# SDADC.net
KiCad netlist of a schematic drawn in Altium Designer
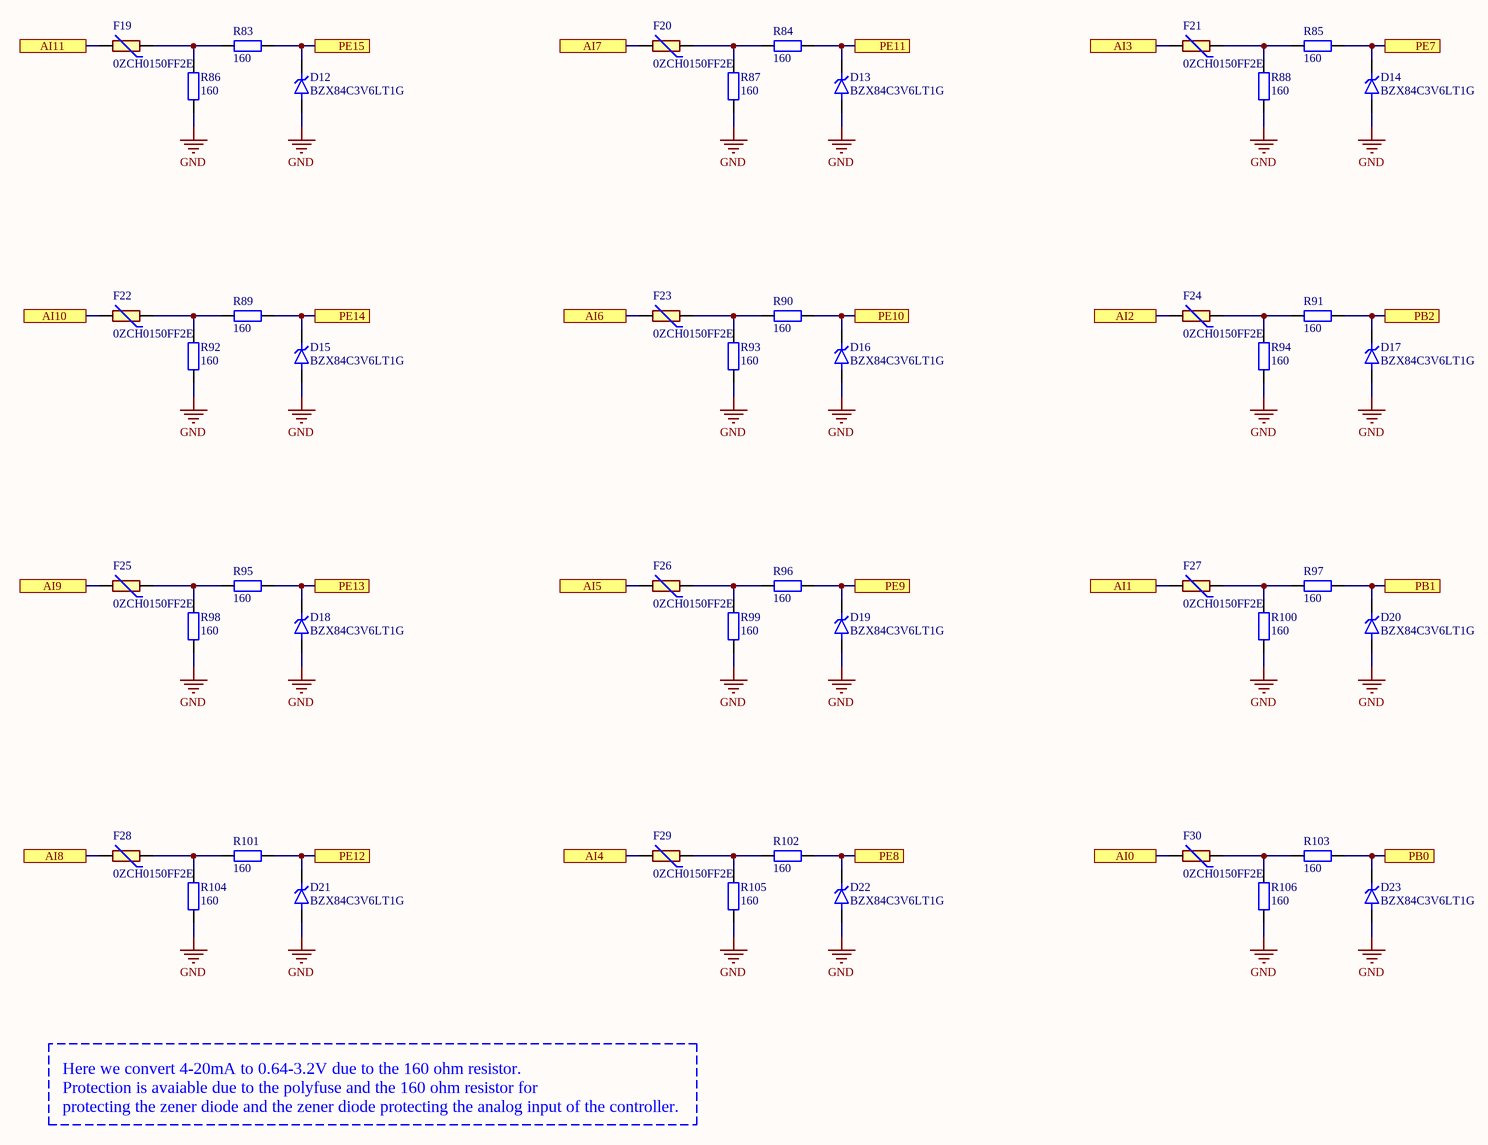
[diagram p0: SDADC.SchDoc]

(export (version "E")
  (design (tool "Eeschema 10.0.6"))
  (components
    (comp (ref "D12")
      (value "BZX84C3V6LT1G")
      (footprint "SOT95P240X111-3N")
      (libsource (lib "BZX84C3V6LT1G") (part "BZX84C3V6LT1G"))
    )
    (comp (ref "D13")
      (value "BZX84C3V6LT1G")
      (footprint "SOT95P240X111-3N")
      (libsource (lib "BZX84C3V6LT1G") (part "BZX84C3V6LT1G"))
    )
    (comp (ref "D14")
      (value "BZX84C3V6LT1G")
      (footprint "SOT95P240X111-3N")
      (libsource (lib "BZX84C3V6LT1G") (part "BZX84C3V6LT1G"))
    )
    (comp (ref "D15")
      (value "BZX84C3V6LT1G")
      (footprint "SOT95P240X111-3N")
      (libsource (lib "BZX84C3V6LT1G") (part "BZX84C3V6LT1G"))
    )
    (comp (ref "D16")
      (value "BZX84C3V6LT1G")
      (footprint "SOT95P240X111-3N")
      (libsource (lib "BZX84C3V6LT1G") (part "BZX84C3V6LT1G"))
    )
    (comp (ref "D17")
      (value "BZX84C3V6LT1G")
      (footprint "SOT95P240X111-3N")
      (libsource (lib "BZX84C3V6LT1G") (part "BZX84C3V6LT1G"))
    )
    (comp (ref "D18")
      (value "BZX84C3V6LT1G")
      (footprint "SOT95P240X111-3N")
      (libsource (lib "BZX84C3V6LT1G") (part "BZX84C3V6LT1G"))
    )
    (comp (ref "D19")
      (value "BZX84C3V6LT1G")
      (footprint "SOT95P240X111-3N")
      (libsource (lib "BZX84C3V6LT1G") (part "BZX84C3V6LT1G"))
    )
    (comp (ref "D20")
      (value "BZX84C3V6LT1G")
      (footprint "SOT95P240X111-3N")
      (libsource (lib "BZX84C3V6LT1G") (part "BZX84C3V6LT1G"))
    )
    (comp (ref "D21")
      (value "BZX84C3V6LT1G")
      (footprint "SOT95P240X111-3N")
      (libsource (lib "BZX84C3V6LT1G") (part "BZX84C3V6LT1G"))
    )
    (comp (ref "D22")
      (value "BZX84C3V6LT1G")
      (footprint "SOT95P240X111-3N")
      (libsource (lib "BZX84C3V6LT1G") (part "BZX84C3V6LT1G"))
    )
    (comp (ref "D23")
      (value "BZX84C3V6LT1G")
      (footprint "SOT95P240X111-3N")
      (libsource (lib "BZX84C3V6LT1G") (part "BZX84C3V6LT1G"))
    )
    (comp (ref "F19")
      (value "0ZCH0150FF2E")
      (footprint "FUSC3225X90N")
      (description "1210 SMT PPTC ¦ 1.50 Ih ¦ 6V")
      (fields (field (name "MF") "Bel Fuse"))
      (libsource (lib "") (part "0ZCH0150FF2E_1"))
    )
    (comp (ref "F20")
      (value "0ZCH0150FF2E")
      (footprint "FUSC3225X90N")
      (description "1210 SMT PPTC ¦ 1.50 Ih ¦ 6V")
      (fields (field (name "MF") "Bel Fuse"))
      (libsource (lib "") (part "0ZCH0150FF2E_1"))
    )
    (comp (ref "F21")
      (value "0ZCH0150FF2E")
      (footprint "FUSC3225X90N")
      (description "1210 SMT PPTC ¦ 1.50 Ih ¦ 6V")
      (fields (field (name "MF") "Bel Fuse"))
      (libsource (lib "0ZCH0150FF2E") (part "0ZCH0150FF2E"))
    )
    (comp (ref "F22")
      (value "0ZCH0150FF2E")
      (footprint "FUSC3225X90N")
      (description "1210 SMT PPTC ¦ 1.50 Ih ¦ 6V")
      (fields (field (name "MF") "Bel Fuse"))
      (libsource (lib "") (part "0ZCH0150FF2E_1"))
    )
    (comp (ref "F23")
      (value "0ZCH0150FF2E")
      (footprint "FUSC3225X90N")
      (description "1210 SMT PPTC ¦ 1.50 Ih ¦ 6V")
      (fields (field (name "MF") "Bel Fuse"))
      (libsource (lib "") (part "0ZCH0150FF2E_1"))
    )
    (comp (ref "F24")
      (value "0ZCH0150FF2E")
      (footprint "FUSC3225X90N")
      (description "1210 SMT PPTC ¦ 1.50 Ih ¦ 6V")
      (fields (field (name "MF") "Bel Fuse"))
      (libsource (lib "0ZCH0150FF2E") (part "0ZCH0150FF2E"))
    )
    (comp (ref "F25")
      (value "0ZCH0150FF2E")
      (footprint "FUSC3225X90N")
      (description "1210 SMT PPTC ¦ 1.50 Ih ¦ 6V")
      (fields (field (name "MF") "Bel Fuse"))
      (libsource (lib "") (part "0ZCH0150FF2E_1"))
    )
    (comp (ref "F26")
      (value "0ZCH0150FF2E")
      (footprint "FUSC3225X90N")
      (description "1210 SMT PPTC ¦ 1.50 Ih ¦ 6V")
      (fields (field (name "MF") "Bel Fuse"))
      (libsource (lib "") (part "0ZCH0150FF2E_1"))
    )
    (comp (ref "F27")
      (value "0ZCH0150FF2E")
      (footprint "FUSC3225X90N")
      (description "1210 SMT PPTC ¦ 1.50 Ih ¦ 6V")
      (fields (field (name "MF") "Bel Fuse"))
      (libsource (lib "0ZCH0150FF2E") (part "0ZCH0150FF2E"))
    )
    (comp (ref "F28")
      (value "0ZCH0150FF2E")
      (footprint "FUSC3225X90N")
      (description "1210 SMT PPTC ¦ 1.50 Ih ¦ 6V")
      (fields (field (name "MF") "Bel Fuse"))
      (libsource (lib "") (part "0ZCH0150FF2E_1"))
    )
    (comp (ref "F29")
      (value "0ZCH0150FF2E")
      (footprint "FUSC3225X90N")
      (description "1210 SMT PPTC ¦ 1.50 Ih ¦ 6V")
      (fields (field (name "MF") "Bel Fuse"))
      (libsource (lib "") (part "0ZCH0150FF2E_1"))
    )
    (comp (ref "F30")
      (value "0ZCH0150FF2E")
      (footprint "FUSC3225X90N")
      (description "1210 SMT PPTC ¦ 1.50 Ih ¦ 6V")
      (fields (field (name "MF") "Bel Fuse"))
      (libsource (lib "0ZCH0150FF2E") (part "0ZCH0150FF2E"))
    )
    (comp (ref "R83")
      (value "160")
      (footprint "tro smd 0603")
      (description "RES")
      (libsource (lib "AUSB") (part "Tro 0603 1% 10k"))
    )
    (comp (ref "R84")
      (value "160")
      (footprint "tro smd 0603")
      (description "RES")
      (libsource (lib "AUSB") (part "Tro 0603 1% 10k"))
    )
    (comp (ref "R85")
      (value "160")
      (footprint "tro smd 0603")
      (description "RES")
      (libsource (lib "AUSB") (part "Tro 0603 1% 10k"))
    )
    (comp (ref "R86")
      (value "160")
      (footprint "tro smd 0603")
      (description "RES")
      (libsource (lib "AUSB") (part "Tro 0603 1% 10k"))
    )
    (comp (ref "R87")
      (value "160")
      (footprint "tro smd 0603")
      (description "RES")
      (libsource (lib "AUSB") (part "Tro 0603 1% 10k"))
    )
    (comp (ref "R88")
      (value "160")
      (footprint "tro smd 0603")
      (description "RES")
      (libsource (lib "AUSB") (part "Tro 0603 1% 10k"))
    )
    (comp (ref "R89")
      (value "160")
      (footprint "tro smd 0603")
      (description "RES")
      (libsource (lib "AUSB") (part "Tro 0603 1% 10k"))
    )
    (comp (ref "R90")
      (value "160")
      (footprint "tro smd 0603")
      (description "RES")
      (libsource (lib "AUSB") (part "Tro 0603 1% 10k"))
    )
    (comp (ref "R91")
      (value "160")
      (footprint "tro smd 0603")
      (description "RES")
      (libsource (lib "AUSB") (part "Tro 0603 1% 10k"))
    )
    (comp (ref "R92")
      (value "160")
      (footprint "tro smd 0603")
      (description "RES")
      (libsource (lib "AUSB") (part "Tro 0603 1% 10k"))
    )
    (comp (ref "R93")
      (value "160")
      (footprint "tro smd 0603")
      (description "RES")
      (libsource (lib "AUSB") (part "Tro 0603 1% 10k"))
    )
    (comp (ref "R94")
      (value "160")
      (footprint "tro smd 0603")
      (description "RES")
      (libsource (lib "AUSB") (part "Tro 0603 1% 10k"))
    )
    (comp (ref "R95")
      (value "160")
      (footprint "tro smd 0603")
      (description "RES")
      (libsource (lib "AUSB") (part "Tro 0603 1% 10k"))
    )
    (comp (ref "R96")
      (value "160")
      (footprint "tro smd 0603")
      (description "RES")
      (libsource (lib "AUSB") (part "Tro 0603 1% 10k"))
    )
    (comp (ref "R97")
      (value "160")
      (footprint "tro smd 0603")
      (description "RES")
      (libsource (lib "AUSB") (part "Tro 0603 1% 10k"))
    )
    (comp (ref "R98")
      (value "160")
      (footprint "tro smd 0603")
      (description "RES")
      (libsource (lib "AUSB") (part "Tro 0603 1% 10k"))
    )
    (comp (ref "R99")
      (value "160")
      (footprint "tro smd 0603")
      (description "RES")
      (libsource (lib "AUSB") (part "Tro 0603 1% 10k"))
    )
    (comp (ref "R100")
      (value "160")
      (footprint "tro smd 0603")
      (description "RES")
      (libsource (lib "AUSB") (part "Tro 0603 1% 10k"))
    )
    (comp (ref "R101")
      (value "160")
      (footprint "tro smd 0603")
      (description "RES")
      (libsource (lib "AUSB") (part "Tro 0603 1% 10k"))
    )
    (comp (ref "R102")
      (value "160")
      (footprint "tro smd 0603")
      (description "RES")
      (libsource (lib "AUSB") (part "Tro 0603 1% 10k"))
    )
    (comp (ref "R103")
      (value "160")
      (footprint "tro smd 0603")
      (description "RES")
      (libsource (lib "AUSB") (part "Tro 0603 1% 10k"))
    )
    (comp (ref "R104")
      (value "160")
      (footprint "tro smd 0603")
      (description "RES")
      (libsource (lib "AUSB") (part "Tro 0603 1% 10k"))
    )
    (comp (ref "R105")
      (value "160")
      (footprint "tro smd 0603")
      (description "RES")
      (libsource (lib "AUSB") (part "Tro 0603 1% 10k"))
    )
    (comp (ref "R106")
      (value "160")
      (footprint "tro smd 0603")
      (description "RES")
      (libsource (lib "AUSB") (part "Tro 0603 1% 10k"))
    )
  )
  (nets
    (net (code "1") (name "/AI0") (class "Default")
      (node (ref "F30") (pin "2") (pinfunction "2_2") (pintype "passive"))
    )
    (net (code "2") (name "/AI1") (class "Default")
      (node (ref "F27") (pin "2") (pinfunction "2_2") (pintype "passive"))
    )
    (net (code "3") (name "/AI2") (class "Default")
      (node (ref "F24") (pin "2") (pinfunction "2_2") (pintype "passive"))
    )
    (net (code "4") (name "/AI3") (class "Default")
      (node (ref "F21") (pin "2") (pinfunction "2_2") (pintype "passive"))
    )
    (net (code "5") (name "/AI4") (class "Default")
      (node (ref "F29") (pin "2") (pinfunction "2_2") (pintype "passive"))
    )
    (net (code "6") (name "/AI5") (class "Default")
      (node (ref "F26") (pin "2") (pinfunction "2_2") (pintype "passive"))
    )
    (net (code "7") (name "/AI6") (class "Default")
      (node (ref "F23") (pin "2") (pinfunction "2_2") (pintype "passive"))
    )
    (net (code "8") (name "/AI7") (class "Default")
      (node (ref "F20") (pin "2") (pinfunction "2_2") (pintype "passive"))
    )
    (net (code "9") (name "/AI8") (class "Default")
      (node (ref "F28") (pin "2") (pinfunction "2_2") (pintype "passive"))
    )
    (net (code "10") (name "/AI9") (class "Default")
      (node (ref "F25") (pin "2") (pinfunction "2_2") (pintype "passive"))
    )
    (net (code "11") (name "/AI10") (class "Default")
      (node (ref "F22") (pin "2") (pinfunction "2_2") (pintype "passive"))
    )
    (net (code "12") (name "/AI11") (class "Default")
      (node (ref "F19") (pin "2") (pinfunction "2_2") (pintype "passive"))
    )
    (net (code "13") (name "/PB0") (class "Default")
      (node (ref "D23") (pin "3") (pinfunction "K_3") (pintype "passive"))
      (node (ref "R103") (pin "2") (pinfunction "2_2") (pintype "passive"))
    )
    (net (code "14") (name "/PB1") (class "Default")
      (node (ref "D20") (pin "3") (pinfunction "K_3") (pintype "passive"))
      (node (ref "R97") (pin "2") (pinfunction "2_2") (pintype "passive"))
    )
    (net (code "15") (name "/PB2") (class "Default")
      (node (ref "D17") (pin "3") (pinfunction "K_3") (pintype "passive"))
      (node (ref "R91") (pin "2") (pinfunction "2_2") (pintype "passive"))
    )
    (net (code "16") (name "/PE7") (class "Default")
      (node (ref "D14") (pin "3") (pinfunction "K_3") (pintype "passive"))
      (node (ref "R85") (pin "2") (pinfunction "2_2") (pintype "passive"))
    )
    (net (code "17") (name "/PE8") (class "Default")
      (node (ref "D22") (pin "3") (pinfunction "K_3") (pintype "passive"))
      (node (ref "R102") (pin "2") (pinfunction "2_2") (pintype "passive"))
    )
    (net (code "18") (name "/PE9") (class "Default")
      (node (ref "D19") (pin "3") (pinfunction "K_3") (pintype "passive"))
      (node (ref "R96") (pin "2") (pinfunction "2_2") (pintype "passive"))
    )
    (net (code "19") (name "/PE10") (class "Default")
      (node (ref "D16") (pin "3") (pinfunction "K_3") (pintype "passive"))
      (node (ref "R90") (pin "2") (pinfunction "2_2") (pintype "passive"))
    )
    (net (code "20") (name "/PE11") (class "Default")
      (node (ref "D13") (pin "3") (pinfunction "K_3") (pintype "passive"))
      (node (ref "R84") (pin "2") (pinfunction "2_2") (pintype "passive"))
    )
    (net (code "21") (name "/PE12") (class "Default")
      (node (ref "D21") (pin "3") (pinfunction "K_3") (pintype "passive"))
      (node (ref "R101") (pin "2") (pinfunction "2_2") (pintype "passive"))
    )
    (net (code "22") (name "/PE13") (class "Default")
      (node (ref "D18") (pin "3") (pinfunction "K_3") (pintype "passive"))
      (node (ref "R95") (pin "2") (pinfunction "2_2") (pintype "passive"))
    )
    (net (code "23") (name "/PE14") (class "Default")
      (node (ref "D15") (pin "3") (pinfunction "K_3") (pintype "passive"))
      (node (ref "R89") (pin "2") (pinfunction "2_2") (pintype "passive"))
    )
    (net (code "24") (name "/PE15") (class "Default")
      (node (ref "D12") (pin "3") (pinfunction "K_3") (pintype "passive"))
      (node (ref "R83") (pin "2") (pinfunction "2_2") (pintype "passive"))
    )
    (net (code "25") (name "GND") (class "Default")
      (node (ref "D12") (pin "1") (pinfunction "A_1") (pintype "passive"))
      (node (ref "D13") (pin "1") (pinfunction "A_1") (pintype "passive"))
      (node (ref "D14") (pin "1") (pinfunction "A_1") (pintype "passive"))
      (node (ref "D15") (pin "1") (pinfunction "A_1") (pintype "passive"))
      (node (ref "D16") (pin "1") (pinfunction "A_1") (pintype "passive"))
      (node (ref "D17") (pin "1") (pinfunction "A_1") (pintype "passive"))
      (node (ref "D18") (pin "1") (pinfunction "A_1") (pintype "passive"))
      (node (ref "D19") (pin "1") (pinfunction "A_1") (pintype "passive"))
      (node (ref "D20") (pin "1") (pinfunction "A_1") (pintype "passive"))
      (node (ref "D21") (pin "1") (pinfunction "A_1") (pintype "passive"))
      (node (ref "D22") (pin "1") (pinfunction "A_1") (pintype "passive"))
      (node (ref "D23") (pin "1") (pinfunction "A_1") (pintype "passive"))
      (node (ref "R100") (pin "1") (pinfunction "1_1") (pintype "passive"))
      (node (ref "R104") (pin "1") (pinfunction "1_1") (pintype "passive"))
      (node (ref "R105") (pin "1") (pinfunction "1_1") (pintype "passive"))
      (node (ref "R106") (pin "1") (pinfunction "1_1") (pintype "passive"))
      (node (ref "R86") (pin "1") (pinfunction "1_1") (pintype "passive"))
      (node (ref "R87") (pin "1") (pinfunction "1_1") (pintype "passive"))
      (node (ref "R88") (pin "1") (pinfunction "1_1") (pintype "passive"))
      (node (ref "R92") (pin "1") (pinfunction "1_1") (pintype "passive"))
      (node (ref "R93") (pin "1") (pinfunction "1_1") (pintype "passive"))
      (node (ref "R94") (pin "1") (pinfunction "1_1") (pintype "passive"))
      (node (ref "R98") (pin "1") (pinfunction "1_1") (pintype "passive"))
      (node (ref "R99") (pin "1") (pinfunction "1_1") (pintype "passive"))
    )
    (net (code "26") (name "Net-(F19-Pad1)") (class "Default")
      (node (ref "F19") (pin "1") (pinfunction "1_1") (pintype "passive"))
      (node (ref "R83") (pin "1") (pinfunction "1_1") (pintype "passive"))
      (node (ref "R86") (pin "2") (pinfunction "2_2") (pintype "passive"))
    )
    (net (code "27") (name "Net-(F20-Pad1)") (class "Default")
      (node (ref "F20") (pin "1") (pinfunction "1_1") (pintype "passive"))
      (node (ref "R84") (pin "1") (pinfunction "1_1") (pintype "passive"))
      (node (ref "R87") (pin "2") (pinfunction "2_2") (pintype "passive"))
    )
    (net (code "28") (name "Net-(F21-Pad1)") (class "Default")
      (node (ref "F21") (pin "1") (pinfunction "1_1") (pintype "passive"))
      (node (ref "R85") (pin "1") (pinfunction "1_1") (pintype "passive"))
      (node (ref "R88") (pin "2") (pinfunction "2_2") (pintype "passive"))
    )
    (net (code "29") (name "Net-(F22-Pad1)") (class "Default")
      (node (ref "F22") (pin "1") (pinfunction "1_1") (pintype "passive"))
      (node (ref "R89") (pin "1") (pinfunction "1_1") (pintype "passive"))
      (node (ref "R92") (pin "2") (pinfunction "2_2") (pintype "passive"))
    )
    (net (code "30") (name "Net-(F23-Pad1)") (class "Default")
      (node (ref "F23") (pin "1") (pinfunction "1_1") (pintype "passive"))
      (node (ref "R90") (pin "1") (pinfunction "1_1") (pintype "passive"))
      (node (ref "R93") (pin "2") (pinfunction "2_2") (pintype "passive"))
    )
    (net (code "31") (name "Net-(F24-Pad1)") (class "Default")
      (node (ref "F24") (pin "1") (pinfunction "1_1") (pintype "passive"))
      (node (ref "R91") (pin "1") (pinfunction "1_1") (pintype "passive"))
      (node (ref "R94") (pin "2") (pinfunction "2_2") (pintype "passive"))
    )
    (net (code "32") (name "Net-(F25-Pad1)") (class "Default")
      (node (ref "F25") (pin "1") (pinfunction "1_1") (pintype "passive"))
      (node (ref "R95") (pin "1") (pinfunction "1_1") (pintype "passive"))
      (node (ref "R98") (pin "2") (pinfunction "2_2") (pintype "passive"))
    )
    (net (code "33") (name "Net-(F26-Pad1)") (class "Default")
      (node (ref "F26") (pin "1") (pinfunction "1_1") (pintype "passive"))
      (node (ref "R96") (pin "1") (pinfunction "1_1") (pintype "passive"))
      (node (ref "R99") (pin "2") (pinfunction "2_2") (pintype "passive"))
    )
    (net (code "34") (name "Net-(F27-Pad1)") (class "Default")
      (node (ref "F27") (pin "1") (pinfunction "1_1") (pintype "passive"))
      (node (ref "R100") (pin "2") (pinfunction "2_2") (pintype "passive"))
      (node (ref "R97") (pin "1") (pinfunction "1_1") (pintype "passive"))
    )
    (net (code "35") (name "Net-(F28-Pad1)") (class "Default")
      (node (ref "F28") (pin "1") (pinfunction "1_1") (pintype "passive"))
      (node (ref "R101") (pin "1") (pinfunction "1_1") (pintype "passive"))
      (node (ref "R104") (pin "2") (pinfunction "2_2") (pintype "passive"))
    )
    (net (code "36") (name "Net-(F29-Pad1)") (class "Default")
      (node (ref "F29") (pin "1") (pinfunction "1_1") (pintype "passive"))
      (node (ref "R102") (pin "1") (pinfunction "1_1") (pintype "passive"))
      (node (ref "R105") (pin "2") (pinfunction "2_2") (pintype "passive"))
    )
    (net (code "37") (name "Net-(F30-Pad1)") (class "Default")
      (node (ref "F30") (pin "1") (pinfunction "1_1") (pintype "passive"))
      (node (ref "R103") (pin "1") (pinfunction "1_1") (pintype "passive"))
      (node (ref "R106") (pin "2") (pinfunction "2_2") (pintype "passive"))
    )
  )
)
